# ESP_with_usb.net
KiCad netlist of a schematic drawn in Altium Designer
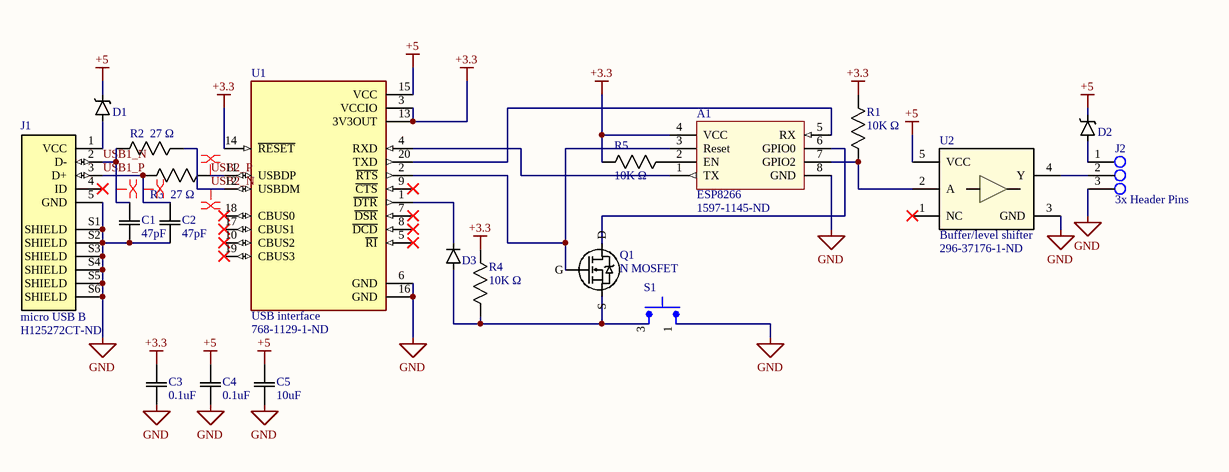
[diagram p0: ESP_with_usb.SchDoc]

(export (version "E")
  (design (tool "Eeschema 10.0.6"))
  (components
    (comp (ref "A1")
      (value "ESP8266")
      (footprint "ESP8266")
      (description "RX TXRX MODULE WIFI TRACE ANT TH")
      (fields (field (name "SUPPLIER PART NUMBER 1") "1597-1145-ND"))
      (libsource (lib "ESP_helper") (part "ESP8266"))
    )
    (comp (ref "C1")
      (value "47pF")
      (footprint "0603")
      (description "CAP CER 47PF 100V C0G/NP0 0603")
      (fields
        (field (name "MANUFACTURER_PART_NUMBER") "CC0805KRX7R9BB104")
        (field (name "COPYRIGHT") "Copyright (C) 2018 Accelerated Designs. All rights reserved")
      )
      (libsource (lib "ESP_helper") (part "CL10C470JC8NNNC"))
    )
    (comp (ref "C2")
      (value "47pF")
      (footprint "0603")
      (description "CAP CER 47PF 100V C0G/NP0 0603")
      (fields
        (field (name "MANUFACTURER_PART_NUMBER") "CC0805KRX7R9BB104")
        (field (name "COPYRIGHT") "Copyright (C) 2018 Accelerated Designs. All rights reserved")
      )
      (libsource (lib "ESP_helper") (part "CL10C470JC8NNNC"))
    )
    (comp (ref "C3")
      (value "0.1uF")
      (footprint "0603")
      (description "CAP CER 0.1UF 50V X7R 0603")
      (fields
        (field (name "MANUFACTURER_PART_NUMBER") "CC0805KRX7R9BB104")
        (field (name "COPYRIGHT") "Copyright (C) 2018 Accelerated Designs. All rights reserved")
      )
      (libsource (lib "ESP_helper") (part "CL10B104KB8NNNC"))
    )
    (comp (ref "C4")
      (value "0.1uF")
      (footprint "0603")
      (description "CAP CER 0.1UF 50V X7R 0603")
      (fields
        (field (name "MANUFACTURER_PART_NUMBER") "CC0805KRX7R9BB104")
        (field (name "COPYRIGHT") "Copyright (C) 2018 Accelerated Designs. All rights reserved")
      )
      (libsource (lib "ESP_helper") (part "CL10B104KB8NNNC"))
    )
    (comp (ref "C5")
      (value "10uF")
      (footprint "0603")
      (description "CAP CER 10UF 10V X5R 0603")
      (fields
        (field (name "MANUFACTURER_PART_NUMBER") "CC0805KRX7R9BB104")
        (field (name "COPYRIGHT") "Copyright (C) 2018 Accelerated Designs. All rights reserved")
      )
      (libsource (lib "ESP_helper") (part "0603ZD106KAT2A"))
    )
    (comp (ref "D1")
      (value "Diode, Schottky")
      (footprint "SOD-523")
      (description "DIODE SCHOTTKY 30V 200MA SOD523")
      (fields (field (name "MP") "BAT20JFILM") (field (name "MF") "STMicroelectronics"))
      (libsource (lib "ESP_helper") (part "RB520S30T1G"))
    )
    (comp (ref "D2")
      (value "Diode, Schottky")
      (footprint "SOD-523")
      (description "DIODE SCHOTTKY 30V 200MA SOD523")
      (fields (field (name "MP") "BAT20JFILM") (field (name "MF") "STMicroelectronics"))
      (libsource (lib "ESP_helper") (part "RB520S30T1G"))
    )
    (comp (ref "D3")
      (value "Diode")
      (footprint "SOD-523")
      (description "DIODE GEN PURP 75V 150MA SOD523")
      (fields (field (name "MP") "BAT20JFILM") (field (name "MF") "STMicroelectronics"))
      (libsource (lib "ESP_helper") (part "1N4148X-TP"))
    )
    (comp (ref "J1")
      (value "micro USB B")
      (footprint "Micro USB B (rev 2)")
      (description "CONN RCPT USB2.0 MICRO B SMD R/A")
      (fields
        (field (name "MANUFACTURER_PART_NUMBER") "ZX62D-B-5P8(30)")
        (field (name "SUPPLIER PART NUMBER 1") "H125272CT-ND")
        (field (name "COPYRIGHT") "Copyright (C) 2018 Accelerated Designs. All rights reserved")
      )
      (libsource (lib "ESP_helper") (part "ZX62D-B-5P8(30)"))
    )
    (comp (ref "J2")
      (value "3x Header Pins")
      (footprint "3 HEADER PIN 90 DEG")
      (description "CONN HEADER VERT 5POS 2.54MM")
      (fields
        (field (name "MANUFACTURER_PART_NUMBER") "77311-818-36LF")
        (field (name "COPYRIGHT") "Copyright (C) 2018 Accelerated Designs. All rights reserved")
      )
      (libsource (lib "ESP_helper") (part "3x Header Pin"))
    )
    (comp (ref "Q1")
      (value "N MOSFET")
      (footprint "SOT-323")
      (description "MOSFET N-CH 60V 0.31A SOT323")
      (fields
        (field (name "MANUFACTURER_PART_NUMBER") "2N7002,215")
        (field (name "COPYRIGHT") "Copyright (C) 2018 Accelerated Designs. All rights reserved")
      )
      (libsource (lib "ESP_helper") (part "2N7002PW,115"))
    )
    (comp (ref "R1")
      (value "10K Ω")
      (footprint "0603")
      (description "RES 10K OHM 1% 1/8W 0603")
      (fields
        (field (name "MANUFACTURER_PART_NUMBER") "RC0805FR-0710KL")
        (field (name "COPYRIGHT") "Copyright (C) 2018 Accelerated Designs. All rights reserved")
      )
      (libsource (lib "ESP_helper") (part "RNCP0603FTD10K0"))
    )
    (comp (ref "R2")
      (value "27 Ω")
      (footprint "0603")
      (description "RES SMD 27 OHM 1% 1/10W 0603")
      (fields
        (field (name "MANUFACTURER_PART_NUMBER") "RC0805FR-0710KL")
        (field (name "COPYRIGHT") "Copyright (C) 2018 Accelerated Designs. All rights reserved")
      )
      (libsource (lib "ESP_helper") (part "RC0603FR-0727RL"))
    )
    (comp (ref "R3")
      (value "27 Ω")
      (footprint "0603")
      (description "RES SMD 27 OHM 1% 1/10W 0603")
      (fields
        (field (name "MANUFACTURER_PART_NUMBER") "RC0805FR-0710KL")
        (field (name "COPYRIGHT") "Copyright (C) 2018 Accelerated Designs. All rights reserved")
      )
      (libsource (lib "ESP_helper") (part "RC0603FR-0727RL"))
    )
    (comp (ref "R4")
      (value "10K Ω")
      (footprint "0603")
      (description "RES 10K OHM 1% 1/8W 0603")
      (fields
        (field (name "MANUFACTURER_PART_NUMBER") "RC0805FR-0710KL")
        (field (name "COPYRIGHT") "Copyright (C) 2018 Accelerated Designs. All rights reserved")
      )
      (libsource (lib "ESP_helper") (part "RNCP0603FTD10K0"))
    )
    (comp (ref "R5")
      (value "10K Ω")
      (footprint "0603")
      (description "RES 10K OHM 1% 1/8W 0603")
      (fields
        (field (name "MANUFACTURER_PART_NUMBER") "RC0805FR-0710KL")
        (field (name "COPYRIGHT") "Copyright (C) 2018 Accelerated Designs. All rights reserved")
      )
      (libsource (lib "ESP_helper") (part "RNCP0603FTD10K0"))
    )
    (comp (ref "S1")
      (value "Pushbutton switch")
      (footprint "ESP_helper:KS11R21")
      (description "SWITCH PUSH SPST-NO 0.025A 50V")
      (fields (field (name "MF") "C&K") (field (name "DIGI-KEY_PART_NUMBER") "CKN4078-ND"))
      (libsource (lib "ESP_helper") (part "KS11R27CQD"))
    )
    (comp (ref "U1")
      (value "USB interface")
      (footprint "ESP_helper:20-SSOP")
      (description "USB Bridge, USB to UART USB 2.0 UART Interface 20-SSOP")
      (fields
        (field (name "MP") "FT231XS-R")
        (field (name "MF") "FTDI,")
        (field (name "SUPPLIER PART NUMBER 1") "768-1129-1-ND")
      )
      (libsource (lib "ESP_helper") (part "FT231XS-R"))
    )
    (comp (ref "U2")
      (value "Buffer/level shifter")
      (footprint "SOT-23-5")
      (description "IC BUF NON-INVERT 5.5V SOT23-5")
      (fields
        (field (name "PARTNUMBER") "SN74LV1T34DBV")
        (field (name "MANUFACTURER") "Texas Instruments")
        (field (name "SUPPLIER PART NUMBER 1") "296-37176-1-ND")
        (field (name "COPYRIGHT") "Copyright (C) 2018 Accelerated Designs. All rights reserved")
      )
      (libsource (lib "ESP_helper") (part "SN74LV1T34DBVR"))
    )
  )
  (nets
    (net (code "1") (name "+3.3") (class "Default")
      (node (ref "A1") (pin "4") (pinfunction "VCC_4") (pintype "power_in"))
      (node (ref "C3") (pin "2") (pinfunction "2_2") (pintype "passive"))
      (node (ref "R1") (pin "1") (pinfunction "1_1") (pintype "passive"))
      (node (ref "R4") (pin "1") (pinfunction "1_1") (pintype "passive"))
      (node (ref "R5") (pin "1") (pinfunction "1_1") (pintype "passive"))
      (node (ref "U1") (pin "13") (pinfunction "3V3OUT_13") (pintype "power_in"))
      (node (ref "U1") (pin "14") (pinfunction "~{RESET}_14") (pintype "input"))
      (node (ref "U1") (pin "3") (pinfunction "VCCIO_3") (pintype "power_in"))
    )
    (net (code "2") (name "+5") (class "Default")
      (node (ref "C4") (pin "2") (pinfunction "2_2") (pintype "passive"))
      (node (ref "C5") (pin "2") (pinfunction "2_2") (pintype "passive"))
      (node (ref "D1") (pin "C") (pinfunction "C_C") (pintype "passive"))
      (node (ref "D2") (pin "C") (pinfunction "C_C") (pintype "passive"))
      (node (ref "U1") (pin "15") (pinfunction "VCC_15") (pintype "power_in"))
      (node (ref "U2") (pin "5") (pinfunction "VCC_5") (pintype "power_in"))
    )
    (net (code "3") (name "/USB1_N") (class "Default")
      (node (ref "C1") (pin "2") (pinfunction "2_2") (pintype "passive"))
      (node (ref "J1") (pin "2") (pinfunction "D-_2") (pintype "bidirectional"))
      (node (ref "R2") (pin "2") (pinfunction "2_2") (pintype "passive"))
    )
    (net (code "4") (name "/USB1_P") (class "Default")
      (node (ref "C2") (pin "2") (pinfunction "2_2") (pintype "passive"))
      (node (ref "J1") (pin "3") (pinfunction "D+_3") (pintype "bidirectional"))
      (node (ref "R3") (pin "2") (pinfunction "2_2") (pintype "passive"))
    )
    (net (code "5") (name "/USB2_N") (class "Default")
      (node (ref "R2") (pin "1") (pinfunction "1_1") (pintype "passive"))
      (node (ref "U1") (pin "12") (pinfunction "USBDM_12") (pintype "bidirectional"))
    )
    (net (code "6") (name "/USB2_P") (class "Default")
      (node (ref "R3") (pin "1") (pinfunction "1_1") (pintype "passive"))
      (node (ref "U1") (pin "11") (pinfunction "USBDP_11") (pintype "bidirectional"))
    )
    (net (code "7") (name "GND") (class "Default")
      (node (ref "A1") (pin "8") (pinfunction "GND_8") (pintype "power_in"))
      (node (ref "C1") (pin "1") (pinfunction "1_1") (pintype "passive"))
      (node (ref "C2") (pin "1") (pinfunction "1_1") (pintype "passive"))
      (node (ref "C3") (pin "1") (pinfunction "1_1") (pintype "passive"))
      (node (ref "C4") (pin "1") (pinfunction "1_1") (pintype "passive"))
      (node (ref "C5") (pin "1") (pinfunction "1_1") (pintype "passive"))
      (node (ref "J1") (pin "5") (pinfunction "GND_5") (pintype "power_in"))
      (node (ref "J1") (pin "S1") (pinfunction "SHIELD_S1") (pintype "passive"))
      (node (ref "J1") (pin "S2") (pinfunction "SHIELD_S2") (pintype "passive"))
      (node (ref "J1") (pin "S3") (pinfunction "SHIELD_S3") (pintype "passive"))
      (node (ref "J1") (pin "S4") (pinfunction "SHIELD_S4") (pintype "passive"))
      (node (ref "J1") (pin "S5") (pinfunction "SHIELD_S5") (pintype "passive"))
      (node (ref "J1") (pin "S6") (pinfunction "SHIELD_S6") (pintype "passive"))
      (node (ref "J2") (pin "3") (pinfunction "3_3") (pintype "passive"))
      (node (ref "S1") (pin "1") (pinfunction "1_1") (pintype "passive"))
      (node (ref "U1") (pin "16") (pinfunction "GND_16") (pintype "power_in"))
      (node (ref "U1") (pin "6") (pinfunction "GND_6") (pintype "power_in"))
      (node (ref "U2") (pin "3") (pinfunction "GND_3") (pintype "power_in"))
    )
    (net (code "8") (name "Net-(A1-EN)") (class "Default")
      (node (ref "A1") (pin "2") (pinfunction "EN_2") (pintype "passive"))
      (node (ref "R5") (pin "2") (pinfunction "2_2") (pintype "passive"))
    )
    (net (code "9") (name "Net-(A1-GPIO0)") (class "Default")
      (node (ref "A1") (pin "6") (pinfunction "GPIO0_6") (pintype "passive"))
      (node (ref "Q1") (pin "3") (pinfunction "D_3") (pintype "passive"))
    )
    (net (code "10") (name "Net-(A1-GPIO2)") (class "Default")
      (node (ref "A1") (pin "7") (pinfunction "GPIO2_7") (pintype "passive"))
      (node (ref "R1") (pin "2") (pinfunction "2_2") (pintype "passive"))
      (node (ref "U2") (pin "2") (pinfunction "A_2") (pintype "passive"))
    )
    (net (code "11") (name "Net-(A1-RX)") (class "Default")
      (node (ref "A1") (pin "5") (pinfunction "RX_5") (pintype "input"))
      (node (ref "U1") (pin "20") (pinfunction "TXD_20") (pintype "output"))
    )
    (net (code "12") (name "Net-(A1-Reset)") (class "Default")
      (node (ref "A1") (pin "3") (pinfunction "Reset_3") (pintype "passive"))
      (node (ref "Q1") (pin "1") (pinfunction "G_1") (pintype "passive"))
      (node (ref "U1") (pin "2") (pinfunction "~{RTS}_2") (pintype "output"))
    )
    (net (code "13") (name "Net-(A1-TX)") (class "Default")
      (node (ref "A1") (pin "1") (pinfunction "TX_1") (pintype "output"))
      (node (ref "U1") (pin "4") (pinfunction "RXD_4") (pintype "input"))
    )
    (net (code "14") (name "Net-(D2-PadA)") (class "Default")
      (node (ref "D2") (pin "A") (pinfunction "A_A") (pintype "passive"))
      (node (ref "J2") (pin "1") (pinfunction "1_1") (pintype "passive"))
    )
    (net (code "15") (name "Net-(J1-VCC)") (class "Default")
      (node (ref "D1") (pin "A") (pinfunction "A_A") (pintype "passive"))
      (node (ref "J1") (pin "1") (pinfunction "VCC_1") (pintype "power_in"))
    )
    (net (code "16") (name "Net-(Q1-S)") (class "Default")
      (node (ref "D3") (pin "A") (pinfunction "A_A") (pintype "passive"))
      (node (ref "Q1") (pin "2") (pinfunction "S_2") (pintype "passive"))
      (node (ref "R4") (pin "2") (pinfunction "2_2") (pintype "passive"))
      (node (ref "S1") (pin "3") (pinfunction "3_3") (pintype "passive"))
    )
    (net (code "17") (name "Net-(U1-~{DTR})") (class "Default")
      (node (ref "D3") (pin "C") (pinfunction "C_C") (pintype "passive"))
      (node (ref "U1") (pin "1") (pinfunction "~{DTR}_1") (pintype "output"))
    )
    (net (code "18") (name "Net-(U2-Y)") (class "Default")
      (node (ref "J2") (pin "2") (pinfunction "2_2") (pintype "passive"))
      (node (ref "U2") (pin "4") (pinfunction "Y_4") (pintype "passive"))
    )
    (net (code "19") (name "unconnected-(J1-ID-Pad4)") (class "Default")
      (node (ref "J1") (pin "4") (pinfunction "ID_4") (pintype "passive+no_connect"))
    )
    (net (code "20") (name "unconnected-(U1-CBUS0-Pad18)") (class "Default")
      (node (ref "U1") (pin "18") (pinfunction "CBUS0_18") (pintype "bidirectional+no_connect"))
    )
    (net (code "21") (name "unconnected-(U1-CBUS1-Pad17)") (class "Default")
      (node (ref "U1") (pin "17") (pinfunction "CBUS1_17") (pintype "bidirectional+no_connect"))
    )
    (net (code "22") (name "unconnected-(U1-CBUS2-Pad10)") (class "Default")
      (node (ref "U1") (pin "10") (pinfunction "CBUS2_10") (pintype "bidirectional+no_connect"))
    )
    (net (code "23") (name "unconnected-(U1-CBUS3-Pad19)") (class "Default")
      (node (ref "U1") (pin "19") (pinfunction "CBUS3_19") (pintype "bidirectional+no_connect"))
    )
    (net (code "24") (name "unconnected-(U1-~{CTS}-Pad9)") (class "Default")
      (node (ref "U1") (pin "9") (pinfunction "~{CTS}_9") (pintype "input+no_connect"))
    )
    (net (code "25") (name "unconnected-(U1-~{DCD}-Pad8)") (class "Default")
      (node (ref "U1") (pin "8") (pinfunction "~{DCD}_8") (pintype "input+no_connect"))
    )
    (net (code "26") (name "unconnected-(U1-~{DSR}-Pad7)") (class "Default")
      (node (ref "U1") (pin "7") (pinfunction "~{DSR}_7") (pintype "input+no_connect"))
    )
    (net (code "27") (name "unconnected-(U1-~{RI}-Pad5)") (class "Default")
      (node (ref "U1") (pin "5") (pinfunction "~{RI}_5") (pintype "input+no_connect"))
    )
    (net (code "28") (name "unconnected-(U2-NC-Pad1)") (class "Default")
      (node (ref "U2") (pin "1") (pinfunction "NC_1") (pintype "passive+no_connect"))
    )
  )
)
